# MAX7219MODULE.net
KiCad netlist of a schematic drawn in EAGLE
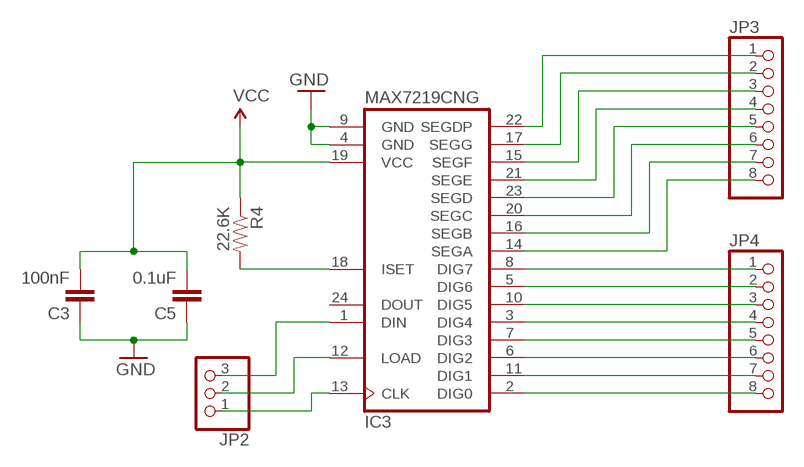
[diagram p0: schematic, sheet 1]

(export (version "E")
  (design (tool "Eeschema 10.0.6"))
  (components
    (comp (ref "C3")
      (value "100nF")
      (footprint "eagle-import:CAP-PTH-SMALL2")
      (libsource (lib "eagle-import") (part "CAPPTH2"))
    )
    (comp (ref "C5")
      (value "0.1uF")
      (footprint "eagle-import:CAP-PTH-SMALL2")
      (libsource (lib "eagle-import") (part "CAPPTH2"))
    )
    (comp (ref "IC3")
      (value "MAX7219CNG")
      (footprint "eagle-import:DIL24-3")
      (fields (field (name "MF") "MAXIM"))
      (libsource (lib "eagle-import") (part "MAX7219CNG"))
    )
    (comp (ref "JP2")
      (value "PINHD-1X3CB")
      (footprint "eagle-import:1X03-CLEANBIG")
      (libsource (lib "eagle-import") (part "PINHD-1X3CB"))
    )
    (comp (ref "JP3")
      (value "PINHD-1X8CLEANBIG")
      (footprint "eagle-import:1X08-CLEANBIG")
      (libsource (lib "eagle-import") (part "PINHD-1X8CLEANBIG"))
    )
    (comp (ref "JP4")
      (value "PINHD-1X8CLEANBIG")
      (footprint "eagle-import:1X08-CLEANBIG")
      (libsource (lib "eagle-import") (part "PINHD-1X8CLEANBIG"))
    )
    (comp (ref "R4")
      (value "22.6K")
      (footprint "eagle-import:AXIAL-0.5")
      (libsource (lib "eagle-import") (part "RESISTORPTH-1/2W"))
    )
  )
  (nets
    (net (code "1") (name "GND") (class "Default")
      (node (ref "C3") (pin "1") (pinfunction "1_1") (pintype "passive"))
      (node (ref "C5") (pin "1") (pinfunction "1_1") (pintype "passive"))
      (node (ref "IC3") (pin "4") (pinfunction "GND_4") (pintype "power_in"))
      (node (ref "IC3") (pin "9") (pinfunction "GND_9") (pintype "power_in"))
    )
    (net (code "2") (name "Net-(IC3-CLK)") (class "Default")
      (node (ref "IC3") (pin "13") (pinfunction "CLK_13") (pintype "input"))
      (node (ref "JP2") (pin "1") (pinfunction "1_1") (pintype "passive"))
    )
    (net (code "3") (name "Net-(IC3-DIG0)") (class "Default")
      (node (ref "IC3") (pin "2") (pinfunction "DIG0_2") (pintype "output"))
      (node (ref "JP4") (pin "8") (pinfunction "8_8") (pintype "passive"))
    )
    (net (code "4") (name "Net-(IC3-DIG1)") (class "Default")
      (node (ref "IC3") (pin "11") (pinfunction "DIG1_11") (pintype "output"))
      (node (ref "JP4") (pin "7") (pinfunction "7_7") (pintype "passive"))
    )
    (net (code "5") (name "Net-(IC3-DIG2)") (class "Default")
      (node (ref "IC3") (pin "6") (pinfunction "DIG2_6") (pintype "output"))
      (node (ref "JP4") (pin "6") (pinfunction "6_6") (pintype "passive"))
    )
    (net (code "6") (name "Net-(IC3-DIG3)") (class "Default")
      (node (ref "IC3") (pin "7") (pinfunction "DIG3_7") (pintype "output"))
      (node (ref "JP4") (pin "5") (pinfunction "5_5") (pintype "passive"))
    )
    (net (code "7") (name "Net-(IC3-DIG4)") (class "Default")
      (node (ref "IC3") (pin "3") (pinfunction "DIG4_3") (pintype "output"))
      (node (ref "JP4") (pin "4") (pinfunction "4_4") (pintype "passive"))
    )
    (net (code "8") (name "Net-(IC3-DIG5)") (class "Default")
      (node (ref "IC3") (pin "10") (pinfunction "DIG5_10") (pintype "output"))
      (node (ref "JP4") (pin "3") (pinfunction "3_3") (pintype "passive"))
    )
    (net (code "9") (name "Net-(IC3-DIG6)") (class "Default")
      (node (ref "IC3") (pin "5") (pinfunction "DIG6_5") (pintype "output"))
      (node (ref "JP4") (pin "2") (pinfunction "2_2") (pintype "passive"))
    )
    (net (code "10") (name "Net-(IC3-DIG7)") (class "Default")
      (node (ref "IC3") (pin "8") (pinfunction "DIG7_8") (pintype "output"))
      (node (ref "JP4") (pin "1") (pinfunction "1_1") (pintype "passive"))
    )
    (net (code "11") (name "Net-(IC3-DIN)") (class "Default")
      (node (ref "IC3") (pin "1") (pinfunction "DIN_1") (pintype "input"))
      (node (ref "JP2") (pin "3") (pinfunction "3_3") (pintype "passive"))
    )
    (net (code "12") (name "Net-(IC3-ISET)") (class "Default")
      (node (ref "IC3") (pin "18") (pinfunction "ISET_18") (pintype "input"))
      (node (ref "R4") (pin "P$2") (pinfunction "2_P$2") (pintype "passive"))
    )
    (net (code "13") (name "Net-(IC3-LOAD)") (class "Default")
      (node (ref "IC3") (pin "12") (pinfunction "LOAD_12") (pintype "input"))
      (node (ref "JP2") (pin "2") (pinfunction "2_2") (pintype "passive"))
    )
    (net (code "14") (name "Net-(IC3-SEGA)") (class "Default")
      (node (ref "IC3") (pin "14") (pinfunction "SEGA_14") (pintype "output"))
      (node (ref "JP3") (pin "8") (pinfunction "8_8") (pintype "passive"))
    )
    (net (code "15") (name "Net-(IC3-SEGB)") (class "Default")
      (node (ref "IC3") (pin "16") (pinfunction "SEGB_16") (pintype "output"))
      (node (ref "JP3") (pin "7") (pinfunction "7_7") (pintype "passive"))
    )
    (net (code "16") (name "Net-(IC3-SEGC)") (class "Default")
      (node (ref "IC3") (pin "20") (pinfunction "SEGC_20") (pintype "output"))
      (node (ref "JP3") (pin "6") (pinfunction "6_6") (pintype "passive"))
    )
    (net (code "17") (name "Net-(IC3-SEGD)") (class "Default")
      (node (ref "IC3") (pin "23") (pinfunction "SEGD_23") (pintype "output"))
      (node (ref "JP3") (pin "5") (pinfunction "5_5") (pintype "passive"))
    )
    (net (code "18") (name "Net-(IC3-SEGDP)") (class "Default")
      (node (ref "IC3") (pin "22") (pinfunction "SEGDP_22") (pintype "output"))
      (node (ref "JP3") (pin "1") (pinfunction "1_1") (pintype "passive"))
    )
    (net (code "19") (name "Net-(IC3-SEGE)") (class "Default")
      (node (ref "IC3") (pin "21") (pinfunction "SEGE_21") (pintype "output"))
      (node (ref "JP3") (pin "4") (pinfunction "4_4") (pintype "passive"))
    )
    (net (code "20") (name "Net-(IC3-SEGF)") (class "Default")
      (node (ref "IC3") (pin "15") (pinfunction "SEGF_15") (pintype "output"))
      (node (ref "JP3") (pin "3") (pinfunction "3_3") (pintype "passive"))
    )
    (net (code "21") (name "Net-(IC3-SEGG)") (class "Default")
      (node (ref "IC3") (pin "17") (pinfunction "SEGG_17") (pintype "output"))
      (node (ref "JP3") (pin "2") (pinfunction "2_2") (pintype "passive"))
    )
    (net (code "22") (name "VCC") (class "Default")
      (node (ref "C3") (pin "2") (pinfunction "2_2") (pintype "passive"))
      (node (ref "C5") (pin "2") (pinfunction "2_2") (pintype "passive"))
      (node (ref "IC3") (pin "19") (pinfunction "VCC_19") (pintype "power_in"))
      (node (ref "R4") (pin "P$1") (pinfunction "1_P$1") (pintype "passive"))
    )
    (net (code "23") (name "unconnected-(IC3-DOUT-Pad24)") (class "Default")
      (node (ref "IC3") (pin "24") (pinfunction "DOUT_24") (pintype "output"))
    )
  )
)
